# headstageNano16LVDS-V1_6.net
KiCad netlist of a schematic drawn in EAGLE
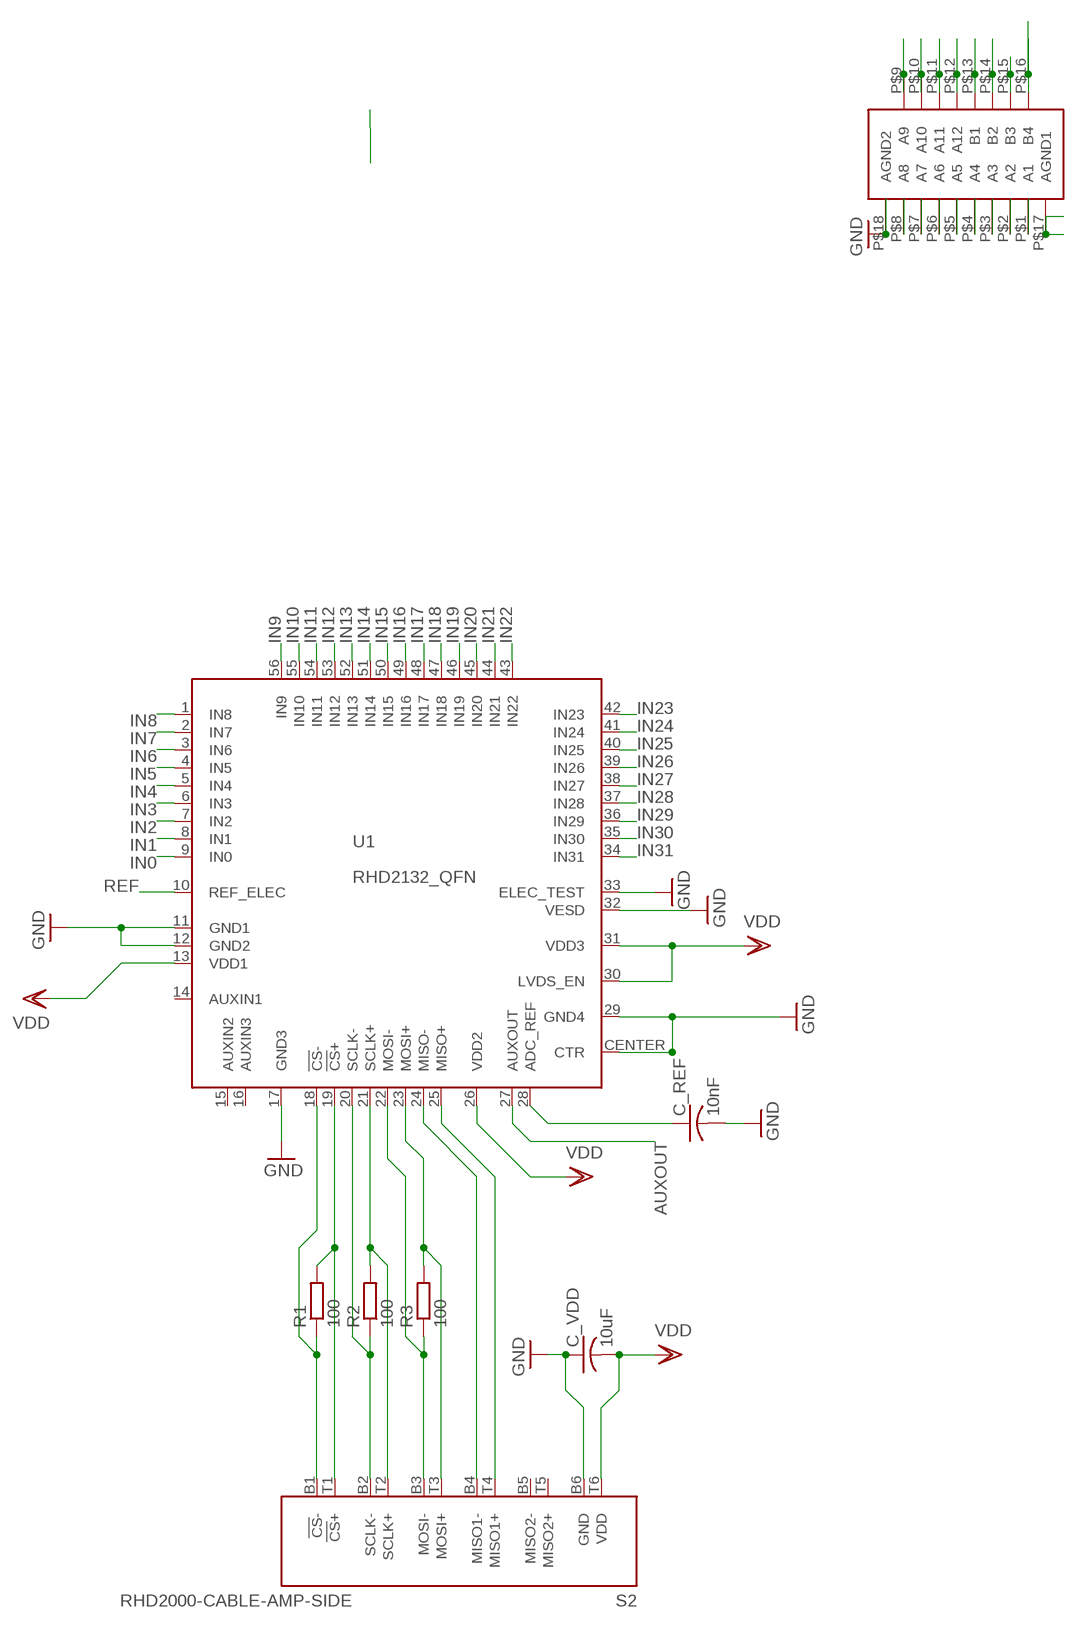
[diagram p0: schematic, sheet 1]

(export (version "E")
  (design (tool "Eeschema 10.0.6"))
  (components
    (comp (ref "C_REF")
      (value "10nF")
      (footprint "eagle-import:C0402K")
      (libsource (lib "eagle-import") (part "C-USC0402K"))
    )
    (comp (ref "C_VDD")
      (value "10uF")
      (footprint "eagle-import:C0402K")
      (libsource (lib "eagle-import") (part "C-USC0402K"))
    )
    (comp (ref "R1")
      (value "100")
      (footprint "eagle-import:R0402")
      (libsource (lib "eagle-import") (part "R-EU_R0402"))
    )
    (comp (ref "R2")
      (value "100")
      (footprint "eagle-import:R0402")
      (libsource (lib "eagle-import") (part "R-EU_R0402"))
    )
    (comp (ref "R3")
      (value "100")
      (footprint "eagle-import:R0402")
      (libsource (lib "eagle-import") (part "R-EU_R0402"))
    )
    (comp (ref "S2")
      (value "RHD2000-CABLE-AMP-SIDE")
      (footprint "eagle-import:OMNETICS_PZN-12-AA")
      (libsource (lib "eagle-import") (part "RHD2000-CABLE-AMP-SIDE"))
    )
    (comp (ref "U$1")
      (value "OMNETICS_FE18")
      (footprint "eagle-import:OMNETICS_FE18")
      (libsource (lib "eagle-import") (part "OMNETICS_FE18"))
    )
    (comp (ref "U1")
      (value "RHD2132_QFN")
      (footprint "eagle-import:QFN56_8_X_8_LARGE")
      (libsource (lib "eagle-import") (part "RHD2132_QFN"))
    )
  )
  (nets
    (net (code "1") (name "/AUXOUT") (class "Default")
      (node (ref "U1") (pin "27") (pinfunction "AUXOUT_27") (pintype "tri_state"))
    )
    (net (code "2") (name "/IN0") (class "Default")
      (node (ref "U1") (pin "9") (pinfunction "IN0_9") (pintype "input"))
    )
    (net (code "3") (name "/IN1") (class "Default")
      (node (ref "U1") (pin "8") (pinfunction "IN1_8") (pintype "input"))
    )
    (net (code "4") (name "/IN2") (class "Default")
      (node (ref "U1") (pin "7") (pinfunction "IN2_7") (pintype "input"))
    )
    (net (code "5") (name "/IN3") (class "Default")
      (node (ref "U1") (pin "6") (pinfunction "IN3_6") (pintype "input"))
    )
    (net (code "6") (name "/IN4") (class "Default")
      (node (ref "U1") (pin "5") (pinfunction "IN4_5") (pintype "input"))
    )
    (net (code "7") (name "/IN5") (class "Default")
      (node (ref "U1") (pin "4") (pinfunction "IN5_4") (pintype "input"))
    )
    (net (code "8") (name "/IN6") (class "Default")
      (node (ref "U1") (pin "3") (pinfunction "IN6_3") (pintype "input"))
    )
    (net (code "9") (name "/IN7") (class "Default")
      (node (ref "U1") (pin "2") (pinfunction "IN7_2") (pintype "input"))
    )
    (net (code "10") (name "/IN8") (class "Default")
      (node (ref "U1") (pin "1") (pinfunction "IN8_1") (pintype "input"))
    )
    (net (code "11") (name "/IN9") (class "Default")
      (node (ref "U1") (pin "56") (pinfunction "IN9_56") (pintype "input"))
    )
    (net (code "12") (name "/IN10") (class "Default")
      (node (ref "U1") (pin "55") (pinfunction "IN10_55") (pintype "input"))
    )
    (net (code "13") (name "/IN11") (class "Default")
      (node (ref "U1") (pin "54") (pinfunction "IN11_54") (pintype "input"))
    )
    (net (code "14") (name "/IN12") (class "Default")
      (node (ref "U1") (pin "53") (pinfunction "IN12_53") (pintype "input"))
    )
    (net (code "15") (name "/IN13") (class "Default")
      (node (ref "U1") (pin "52") (pinfunction "IN13_52") (pintype "input"))
    )
    (net (code "16") (name "/IN14") (class "Default")
      (node (ref "U1") (pin "51") (pinfunction "IN14_51") (pintype "input"))
    )
    (net (code "17") (name "/IN15") (class "Default")
      (node (ref "U1") (pin "50") (pinfunction "IN15_50") (pintype "input"))
    )
    (net (code "18") (name "/IN16") (class "Default")
      (node (ref "U1") (pin "49") (pinfunction "IN16_49") (pintype "input"))
    )
    (net (code "19") (name "/IN17") (class "Default")
      (node (ref "U1") (pin "48") (pinfunction "IN17_48") (pintype "input"))
    )
    (net (code "20") (name "/IN18") (class "Default")
      (node (ref "U1") (pin "47") (pinfunction "IN18_47") (pintype "input"))
    )
    (net (code "21") (name "/IN19") (class "Default")
      (node (ref "U1") (pin "46") (pinfunction "IN19_46") (pintype "input"))
    )
    (net (code "22") (name "/IN20") (class "Default")
      (node (ref "U1") (pin "45") (pinfunction "IN20_45") (pintype "input"))
    )
    (net (code "23") (name "/IN21") (class "Default")
      (node (ref "U1") (pin "44") (pinfunction "IN21_44") (pintype "input"))
    )
    (net (code "24") (name "/IN22") (class "Default")
      (node (ref "U1") (pin "43") (pinfunction "IN22_43") (pintype "input"))
    )
    (net (code "25") (name "/IN23") (class "Default")
      (node (ref "U1") (pin "42") (pinfunction "IN23_42") (pintype "input"))
    )
    (net (code "26") (name "/IN24") (class "Default")
      (node (ref "U1") (pin "41") (pinfunction "IN24_41") (pintype "input"))
    )
    (net (code "27") (name "/IN25") (class "Default")
      (node (ref "U1") (pin "40") (pinfunction "IN25_40") (pintype "input"))
    )
    (net (code "28") (name "/IN26") (class "Default")
      (node (ref "U1") (pin "39") (pinfunction "IN26_39") (pintype "input"))
    )
    (net (code "29") (name "/IN27") (class "Default")
      (node (ref "U1") (pin "38") (pinfunction "IN27_38") (pintype "input"))
    )
    (net (code "30") (name "/IN28") (class "Default")
      (node (ref "U1") (pin "37") (pinfunction "IN28_37") (pintype "input"))
    )
    (net (code "31") (name "/IN29") (class "Default")
      (node (ref "U1") (pin "36") (pinfunction "IN29_36") (pintype "input"))
    )
    (net (code "32") (name "/IN30") (class "Default")
      (node (ref "U1") (pin "35") (pinfunction "IN30_35") (pintype "input"))
    )
    (net (code "33") (name "/IN31") (class "Default")
      (node (ref "U1") (pin "34") (pinfunction "IN31_34") (pintype "input"))
    )
    (net (code "34") (name "/REF") (class "Default")
      (node (ref "U1") (pin "10") (pinfunction "REF_ELEC_10") (pintype "input"))
    )
    (net (code "35") (name "GND") (class "Default")
      (node (ref "C_REF") (pin "2") (pinfunction "2_2") (pintype "passive"))
      (node (ref "C_VDD") (pin "1") (pinfunction "1_1") (pintype "passive"))
      (node (ref "S2") (pin "B6") (pinfunction "GND_B6") (pintype "power_in"))
      (node (ref "U$1") (pin "P$18") (pinfunction "AGND2_P$18") (pintype "bidirectional"))
      (node (ref "U1") (pin "11") (pinfunction "GND1_11") (pintype "power_in"))
      (node (ref "U1") (pin "12") (pinfunction "GND2_12") (pintype "power_in"))
      (node (ref "U1") (pin "17") (pinfunction "GND3_17") (pintype "power_in"))
      (node (ref "U1") (pin "29") (pinfunction "GND4_29") (pintype "power_in"))
      (node (ref "U1") (pin "32") (pinfunction "VESD_32") (pintype "power_in"))
      (node (ref "U1") (pin "33") (pinfunction "ELEC_TEST_33") (pintype "input"))
      (node (ref "U1") (pin "CENTER") (pinfunction "CTR_CENTER") (pintype "power_in"))
    )
    (net (code "36") (name "Net-(S2-MISO1+)") (class "Default")
      (node (ref "S2") (pin "T4") (pinfunction "MISO1+_T4") (pintype "bidirectional"))
      (node (ref "U1") (pin "25") (pinfunction "MISO+_25") (pintype "output"))
    )
    (net (code "37") (name "Net-(S2-MISO1-)") (class "Default")
      (node (ref "S2") (pin "B4") (pinfunction "MISO1-_B4") (pintype "bidirectional"))
      (node (ref "U1") (pin "24") (pinfunction "MISO-_24") (pintype "output"))
    )
    (net (code "38") (name "Net-(S2-MOSI+)") (class "Default")
      (node (ref "R3") (pin "2") (pinfunction "2_2") (pintype "passive"))
      (node (ref "S2") (pin "T3") (pinfunction "MOSI+_T3") (pintype "bidirectional"))
      (node (ref "U1") (pin "23") (pinfunction "MOSI+_23") (pintype "input"))
    )
    (net (code "39") (name "Net-(S2-MOSI-)") (class "Default")
      (node (ref "R3") (pin "1") (pinfunction "1_1") (pintype "passive"))
      (node (ref "S2") (pin "B3") (pinfunction "MOSI-_B3") (pintype "bidirectional"))
      (node (ref "U1") (pin "22") (pinfunction "MOSI-_22") (pintype "input"))
    )
    (net (code "40") (name "Net-(S2-SCLK+)") (class "Default")
      (node (ref "R2") (pin "2") (pinfunction "2_2") (pintype "passive"))
      (node (ref "S2") (pin "T2") (pinfunction "SCLK+_T2") (pintype "bidirectional"))
      (node (ref "U1") (pin "21") (pinfunction "SCLK+_21") (pintype "input"))
    )
    (net (code "41") (name "Net-(S2-SCLK-)") (class "Default")
      (node (ref "R2") (pin "1") (pinfunction "1_1") (pintype "passive"))
      (node (ref "S2") (pin "B2") (pinfunction "SCLK-_B2") (pintype "bidirectional"))
      (node (ref "U1") (pin "20") (pinfunction "SCLK-_20") (pintype "input"))
    )
    (net (code "42") (name "Net-(S2-~{CS}+)") (class "Default")
      (node (ref "R1") (pin "2") (pinfunction "2_2") (pintype "passive"))
      (node (ref "S2") (pin "T1") (pinfunction "~{CS}+_T1") (pintype "bidirectional"))
      (node (ref "U1") (pin "19") (pinfunction "~{CS}+_19") (pintype "input"))
    )
    (net (code "43") (name "Net-(S2-~{CS}-)") (class "Default")
      (node (ref "R1") (pin "1") (pinfunction "1_1") (pintype "passive"))
      (node (ref "S2") (pin "B1") (pinfunction "~{CS}-_B1") (pintype "bidirectional"))
      (node (ref "U1") (pin "18") (pinfunction "~{CS}-_18") (pintype "input"))
    )
    (net (code "44") (name "Net-(U1-ADC_REF)") (class "Default")
      (node (ref "C_REF") (pin "1") (pinfunction "1_1") (pintype "passive"))
      (node (ref "U1") (pin "28") (pinfunction "ADC_REF_28") (pintype "passive"))
    )
    (net (code "45") (name "VDD") (class "Default")
      (node (ref "C_VDD") (pin "2") (pinfunction "2_2") (pintype "passive"))
      (node (ref "S2") (pin "T6") (pinfunction "VDD_T6") (pintype "bidirectional"))
      (node (ref "U1") (pin "13") (pinfunction "VDD1_13") (pintype "power_in"))
      (node (ref "U1") (pin "26") (pinfunction "VDD2_26") (pintype "power_in"))
      (node (ref "U1") (pin "30") (pinfunction "LVDS_EN_30") (pintype "input"))
      (node (ref "U1") (pin "31") (pinfunction "VDD3_31") (pintype "power_in"))
    )
    (net (code "46") (name "unconnected-(S2-MISO2+-PadT5)") (class "Default")
      (node (ref "S2") (pin "T5") (pinfunction "MISO2+_T5") (pintype "bidirectional"))
    )
    (net (code "47") (name "unconnected-(S2-MISO2--PadB5)") (class "Default")
      (node (ref "S2") (pin "B5") (pinfunction "MISO2-_B5") (pintype "bidirectional"))
    )
    (net (code "48") (name "unconnected-(U$1-A1-PadP$1)") (class "Default")
      (node (ref "U$1") (pin "P$1") (pinfunction "A1_P$1") (pintype "bidirectional"))
    )
    (net (code "49") (name "unconnected-(U$1-A2-PadP$2)") (class "Default")
      (node (ref "U$1") (pin "P$2") (pinfunction "A2_P$2") (pintype "bidirectional"))
    )
    (net (code "50") (name "unconnected-(U$1-A3-PadP$3)") (class "Default")
      (node (ref "U$1") (pin "P$3") (pinfunction "A3_P$3") (pintype "bidirectional"))
    )
    (net (code "51") (name "unconnected-(U$1-A4-PadP$4)") (class "Default")
      (node (ref "U$1") (pin "P$4") (pinfunction "A4_P$4") (pintype "bidirectional"))
    )
    (net (code "52") (name "unconnected-(U$1-A5-PadP$5)") (class "Default")
      (node (ref "U$1") (pin "P$5") (pinfunction "A5_P$5") (pintype "bidirectional"))
    )
    (net (code "53") (name "unconnected-(U$1-A6-PadP$6)") (class "Default")
      (node (ref "U$1") (pin "P$6") (pinfunction "A6_P$6") (pintype "bidirectional"))
    )
    (net (code "54") (name "unconnected-(U$1-A7-PadP$7)") (class "Default")
      (node (ref "U$1") (pin "P$7") (pinfunction "A7_P$7") (pintype "bidirectional"))
    )
    (net (code "55") (name "unconnected-(U$1-A8-PadP$8)") (class "Default")
      (node (ref "U$1") (pin "P$8") (pinfunction "A8_P$8") (pintype "bidirectional"))
    )
    (net (code "56") (name "unconnected-(U$1-A9-PadP$9)") (class "Default")
      (node (ref "U$1") (pin "P$9") (pinfunction "A9_P$9") (pintype "bidirectional"))
    )
    (net (code "57") (name "unconnected-(U$1-A10-PadP$10)") (class "Default")
      (node (ref "U$1") (pin "P$10") (pinfunction "A10_P$10") (pintype "bidirectional"))
    )
    (net (code "58") (name "unconnected-(U$1-A11-PadP$11)") (class "Default")
      (node (ref "U$1") (pin "P$11") (pinfunction "A11_P$11") (pintype "bidirectional"))
    )
    (net (code "59") (name "unconnected-(U$1-A12-PadP$12)") (class "Default")
      (node (ref "U$1") (pin "P$12") (pinfunction "A12_P$12") (pintype "bidirectional"))
    )
    (net (code "60") (name "unconnected-(U$1-AGND1-PadP$17)") (class "Default")
      (node (ref "U$1") (pin "P$17") (pinfunction "AGND1_P$17") (pintype "bidirectional"))
    )
    (net (code "61") (name "unconnected-(U$1-B1-PadP$13)") (class "Default")
      (node (ref "U$1") (pin "P$13") (pinfunction "B1_P$13") (pintype "bidirectional"))
    )
    (net (code "62") (name "unconnected-(U$1-B2-PadP$14)") (class "Default")
      (node (ref "U$1") (pin "P$14") (pinfunction "B2_P$14") (pintype "bidirectional"))
    )
    (net (code "63") (name "unconnected-(U$1-B3-PadP$15)") (class "Default")
      (node (ref "U$1") (pin "P$15") (pinfunction "B3_P$15") (pintype "bidirectional"))
    )
    (net (code "64") (name "unconnected-(U$1-B4-PadP$16)") (class "Default")
      (node (ref "U$1") (pin "P$16") (pinfunction "B4_P$16") (pintype "bidirectional"))
    )
    (net (code "65") (name "unconnected-(U1-AUXIN1-Pad14)") (class "Default")
      (node (ref "U1") (pin "14") (pinfunction "AUXIN1_14") (pintype "input"))
    )
    (net (code "66") (name "unconnected-(U1-AUXIN2-Pad15)") (class "Default")
      (node (ref "U1") (pin "15") (pinfunction "AUXIN2_15") (pintype "input"))
    )
    (net (code "67") (name "unconnected-(U1-AUXIN3-Pad16)") (class "Default")
      (node (ref "U1") (pin "16") (pinfunction "AUXIN3_16") (pintype "input"))
    )
  )
)
